# Booster_PA_OUT.net
KiCad netlist of a schematic drawn in Altium Designer
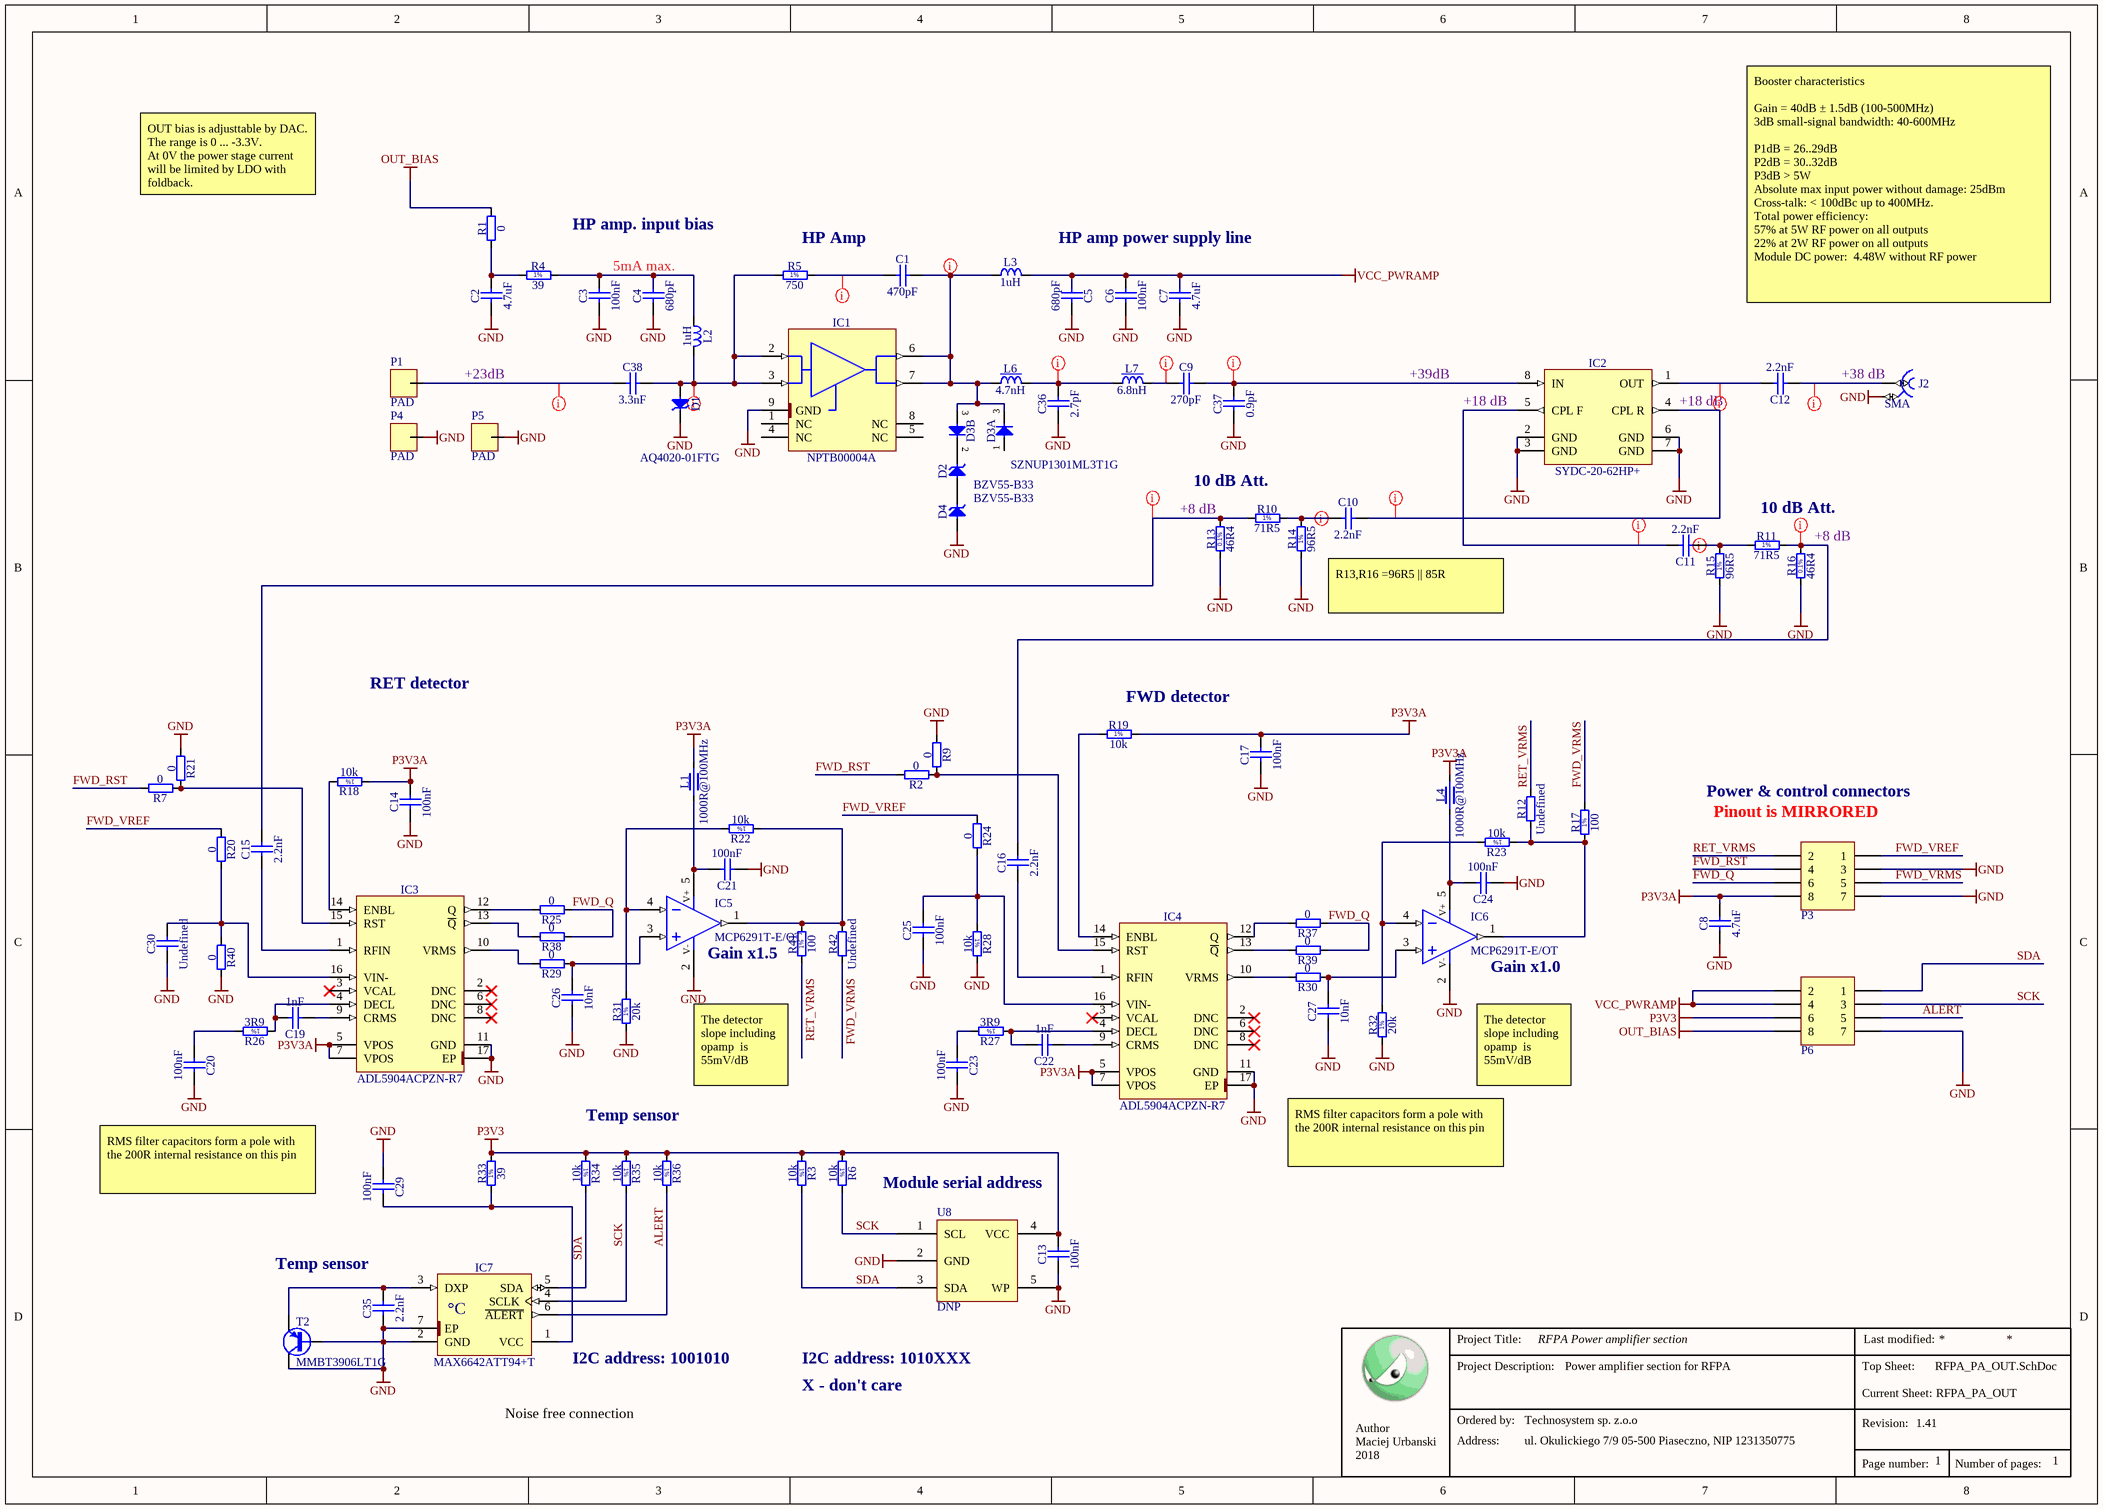
[diagram p0: Booster_PA_OUT.SchDoc]

(export (version "E")
  (design (tool "Eeschema 10.0.6"))
  (components
    (comp (ref "C1")
      (value "470pF")
      (footprint "CAPC1608X87N")
      (description "Non-polarised capacitor")
      (fields (field (name "PART NUMBER") "CC0603_470PF_50V_1%_NP0") (field (name "VOLTAGE") "50V"))
      (libsource (lib "Passives_RC") (part "CC0603_470PF_50V_1%_NP0"))
    )
    (comp (ref "C2")
      (value "4.7uF")
      (footprint "CAPC1709X95N")
      (description "Non-polarised capacitor")
      (fields
        (field (name "MANUFACTURER") "GENERIC")
        (field (name "MANUFACTURER PART NUMBER") "CC0603_4.7UF_16V_10%_X5R")
      )
      (libsource (lib "Capacitors") (part "Capacitor - non polarized"))
    )
    (comp (ref "C3")
      (value "100nF")
      (footprint "CAPC1005X55N")
      (description "Non-polarised capacitor")
      (fields
        (field (name "MANUFACTURER") "GENERIC")
        (field (name "MANUFACTURER PART NUMBER") "CC0402_100NF_50V_10%_X7R")
      )
      (libsource (lib "Capacitors") (part "Capacitor - non polarized"))
    )
    (comp (ref "C4")
      (value "680pF")
      (footprint "CAPC1608X87N")
      (description "Non-polarised capacitor")
      (fields
        (field (name "MANUFACTURER") "GENERIC")
        (field (name "MANUFACTURER PART NUMBER") "CC0603_680PF_50V_5%_NP0")
      )
      (libsource (lib "Capacitors") (part "Capacitor - non polarized"))
    )
    (comp (ref "C5")
      (value "680pF")
      (footprint "CAPC1608X87N")
      (description "Non-polarised capacitor")
      (fields
        (field (name "MANUFACTURER") "GENERIC")
        (field (name "MANUFACTURER PART NUMBER") "CC0603_680PF_50V_5%_NP0")
      )
      (libsource (lib "Capacitors") (part "Capacitor - non polarized"))
    )
    (comp (ref "C6")
      (value "100nF")
      (footprint "CAPC1005X55N")
      (description "Non-polarised capacitor")
      (fields
        (field (name "MANUFACTURER") "GENERIC")
        (field (name "MANUFACTURER PART NUMBER") "CC0402_100NF_50V_10%_X7R")
      )
      (libsource (lib "Capacitors") (part "Capacitor - non polarized"))
    )
    (comp (ref "C7")
      (value "4.7uF")
      (footprint "CAPC3225X270N")
      (description "Non-polarised capacitor")
      (fields (field (name "PART NUMBER") "CC1210_4.7UF_50V_10%_X7R") (field (name "VOLTAGE") "50V"))
      (libsource (lib "Capacitors") (part "Capacitor - non polarized"))
    )
    (comp (ref "C8")
      (value "4.7uF")
      (footprint "CAPC1709X95N")
      (description "Non-polarised capacitor")
      (fields
        (field (name "MANUFACTURER") "GENERIC")
        (field (name "MANUFACTURER PART NUMBER") "CC0603_4.7UF_16V_10%_X5R")
      )
      (libsource (lib "Capacitors") (part "Capacitor - non polarized"))
    )
    (comp (ref "C9")
      (value "270pF")
      (footprint "CAPC1608X87N")
      (description "Non-polarised capacitor")
      (fields (field (name "PART NUMBER") "CC0603_270PF_50V_1%_NP0") (field (name "VOLTAGE") "50V"))
      (libsource (lib "Passives_RC") (part "CC0603_270PF_50V_1%_NP0"))
    )
    (comp (ref "C10")
      (value "2.2nF")
      (footprint "CAPC1608X87N")
      (description "Non-polarised capacitor")
      (fields (field (name "PART NUMBER") "CC0603_2.2NF_50V_5%_C0G") (field (name "VOLTAGE") "50V"))
      (libsource (lib "Capacitors") (part "Capacitor - non polarized"))
    )
    (comp (ref "C11")
      (value "2.2nF")
      (footprint "CAPC1608X87N")
      (description "Non-polarised capacitor")
      (fields
        (field (name "MANUFACTURER") "GENERIC")
        (field (name "MANUFACTURER PART NUMBER") "CC0603_2.2NF_50V_5%_C0G")
      )
      (libsource (lib "Capacitors") (part "Capacitor - non polarized"))
    )
    (comp (ref "C12")
      (value "2.2nF")
      (footprint "CAPC1608X87N")
      (description "Non-polarised capacitor")
      (fields
        (field (name "MANUFACTURER") "GENERIC")
        (field (name "MANUFACTURER PART NUMBER") "CC0603_2.2NF_50V_5%_C0G")
      )
      (libsource (lib "Capacitors") (part "Capacitor - non polarized"))
    )
    (comp (ref "C13")
      (value "100nF")
      (footprint "CAPC1005X55N")
      (description "Non-polarised capacitor")
      (fields
        (field (name "MANUFACTURER") "GENERIC")
        (field (name "MANUFACTURER PART NUMBER") "CC0402_100NF_50V_10%_X7R")
      )
      (libsource (lib "Capacitors") (part "Capacitor - non polarized"))
    )
    (comp (ref "C14")
      (value "100nF")
      (footprint "CAPC1005X55N")
      (description "Non-polarised capacitor")
      (fields
        (field (name "MANUFACTURER") "GENERIC")
        (field (name "MANUFACTURER PART NUMBER") "CC0402_100NF_50V_10%_X7R")
      )
      (libsource (lib "Capacitors") (part "Capacitor - non polarized"))
    )
    (comp (ref "C15")
      (value "2.2nF")
      (footprint "CAPC1608X87N")
      (description "Non-polarised capacitor")
      (fields
        (field (name "MANUFACTURER") "GENERIC")
        (field (name "MANUFACTURER PART NUMBER") "CC0603_2.2NF_50V_5%_C0G")
      )
      (libsource (lib "Capacitors") (part "Capacitor - non polarized"))
    )
    (comp (ref "C16")
      (value "2.2nF")
      (footprint "CAPC1608X87N")
      (description "Non-polarised capacitor")
      (fields
        (field (name "MANUFACTURER") "GENERIC")
        (field (name "MANUFACTURER PART NUMBER") "CC0603_2.2NF_50V_5%_C0G")
      )
      (libsource (lib "Capacitors") (part "Capacitor - non polarized"))
    )
    (comp (ref "C17")
      (value "100nF")
      (footprint "CAPC1005X55N")
      (description "Non-polarised capacitor")
      (fields
        (field (name "MANUFACTURER") "GENERIC")
        (field (name "MANUFACTURER PART NUMBER") "CC0402_100NF_50V_10%_X7R")
      )
      (libsource (lib "Capacitors") (part "Capacitor - non polarized"))
    )
    (comp (ref "C19")
      (value "1nF")
      (footprint "CAPC1005X55N")
      (description "Non-polarised capacitor")
      (fields (field (name "PART NUMBER") "CC0402_1NF_50V_10%_X7R") (field (name "VOLTAGE") "50V"))
      (libsource (lib "Capacitors") (part "Capacitor - non polarized"))
    )
    (comp (ref "C20")
      (value "100nF")
      (footprint "CAPC1005X55N")
      (description "Non-polarised capacitor")
      (fields
        (field (name "MANUFACTURER") "GENERIC")
        (field (name "MANUFACTURER PART NUMBER") "CC0402_100NF_50V_10%_X7R")
      )
      (libsource (lib "Capacitors") (part "Capacitor - non polarized"))
    )
    (comp (ref "C21")
      (value "100nF")
      (footprint "CAPC1005X55N")
      (description "Non-polarised capacitor")
      (fields
        (field (name "MANUFACTURER") "GENERIC")
        (field (name "MANUFACTURER PART NUMBER") "CC0402_100NF_50V_10%_X7R")
      )
      (libsource (lib "Capacitors") (part "Capacitor - non polarized"))
    )
    (comp (ref "C22")
      (value "1nF")
      (footprint "CAPC1005X55N")
      (description "Non-polarised capacitor")
      (fields (field (name "PART NUMBER") "CC0402_1NF_50V_10%_X7R") (field (name "VOLTAGE") "50V"))
      (libsource (lib "Capacitors") (part "Capacitor - non polarized"))
    )
    (comp (ref "C23")
      (value "100nF")
      (footprint "CAPC1005X55N")
      (description "Non-polarised capacitor")
      (fields
        (field (name "MANUFACTURER") "GENERIC")
        (field (name "MANUFACTURER PART NUMBER") "CC0402_100NF_50V_10%_X7R")
      )
      (libsource (lib "Capacitors") (part "Capacitor - non polarized"))
    )
    (comp (ref "C24")
      (value "100nF")
      (footprint "CAPC1005X55N")
      (description "Non-polarised capacitor")
      (fields
        (field (name "MANUFACTURER") "GENERIC")
        (field (name "MANUFACTURER PART NUMBER") "CC0402_100NF_50V_10%_X7R")
      )
      (libsource (lib "Capacitors") (part "Capacitor - non polarized"))
    )
    (comp (ref "C25")
      (value "100nF")
      (footprint "CAPC1005X55N")
      (description "Non-polarised capacitor")
      (fields
        (field (name "MANUFACTURER") "GENERIC")
        (field (name "MANUFACTURER PART NUMBER") "CC0402_100NF_50V_10%_X7R")
      )
      (libsource (lib "Capacitors") (part "Capacitor - non polarized"))
    )
    (comp (ref "C26")
      (value "10nF")
      (footprint "CAPC1005X55N")
      (description "Non-polarised capacitor")
      (fields
        (field (name "MANUFACTURER") "GENERIC")
        (field (name "MANUFACTURER PART NUMBER") "CC0402_10NF_25V_10%_X7R")
      )
      (libsource (lib "Capacitors") (part "Capacitor - non polarized"))
    )
    (comp (ref "C27")
      (value "10nF")
      (footprint "CAPC1005X55N")
      (description "Non-polarised capacitor")
      (fields
        (field (name "MANUFACTURER") "GENERIC")
        (field (name "MANUFACTURER PART NUMBER") "CC0402_10NF_25V_10%_X7R")
      )
      (libsource (lib "Capacitors") (part "Capacitor - non polarized"))
    )
    (comp (ref "C29")
      (value "100nF")
      (footprint "CAPC1005X55N")
      (description "Non-polarised capacitor")
      (fields
        (field (name "MANUFACTURER") "GENERIC")
        (field (name "MANUFACTURER PART NUMBER") "CC0402_100NF_50V_10%_X7R")
      )
      (libsource (lib "Capacitors") (part "Capacitor - non polarized"))
    )
    (comp (ref "C30")
      (value "Undefined")
      (footprint "CAPC1608X90N")
      (description "Non-polarised capacitor")
      (fields (field (name "PART NUMBER") "CC0603_NO-VALUE"))
      (libsource (lib "Capacitors") (part "Capacitor - non polarized"))
    )
    (comp (ref "C35")
      (value "2.2nF")
      (footprint "CAPC1608X87N")
      (description "Non-polarised capacitor")
      (fields
        (field (name "MANUFACTURER") "GENERIC")
        (field (name "MANUFACTURER PART NUMBER") "CC0603_2.2NF_50V_5%_C0G")
      )
      (libsource (lib "Capacitors") (part "Capacitor - non polarized"))
    )
    (comp (ref "C36")
      (value "2.7pF")
      (footprint "CAPC1608X87N")
      (description "Non-polarised capacitor")
      (fields (field (name "PART NUMBER") "CC0603_2.7PF_50V_0.25PF_NP0") (field (name "VOLTAGE") "50V"))
      (libsource (lib "Capacitors") (part "Capacitor - non polarized"))
    )
    (comp (ref "C37")
      (value "0.9pF")
      (footprint "CAPC1608X87N")
      (description "Non-polarised capacitor")
      (fields (field (name "PART NUMBER") "CC0603_0.9PF_50V_0.05PF_NP0") (field (name "VOLTAGE") "50V"))
      (libsource (lib "Passives_RC") (part "CC0603_0.9PF_50V_0.05PF_NP0"))
    )
    (comp (ref "C38")
      (value "3.3nF")
      (footprint "CAPC1608X87N")
      (description "Non-polarised capacitor")
      (fields
        (field (name "MANUFACTURER") "GENERIC")
        (field (name "MANUFACTURER PART NUMBER") "CC0603_3.3NF_50V_5%_C0G")
      )
      (libsource (lib "Capacitors") (part "Capacitor - non polarized"))
    )
    (comp (ref "D1")
      (value "AQ4020-01FTG")
      (footprint "SOD2512X110N")
      (description "4V Transient Voltage Suppressor Diode (Uni-Directional)")
      (fields (field (name "VOLTAGE") "4V") (field (name "POWER") "735W"))
      (libsource (lib "Diodes") (part "D_TVS_AQ4020-01FTG"))
    )
    (comp (ref "D2")
      (value "BZV55-B33")
      (footprint "DIOMELF3515N")
      (description "Zener Diode")
      (fields (field (name "VOLTAGE") "33V") (field (name "POWER") "500mW"))
      (libsource (lib "ICs And Semiconductors") (part "Diode Zener"))
    )
    (comp (ref "D3")
      (value "SZNUP1301ML3T1G")
      (footprint "SOT95P240X110-3N")
      (description "Low Capacitance Diode Array for ESD Protection in a Single Data Line")
      (fields (field (name "VOLTAGE") "70V") (field (name "POWER") "215mA"))
      (libsource (lib "Diodes") (part "D_TVS_SZNUP1301ML3T1G"))
    )
    (comp (ref "D4")
      (value "BZV55-B33")
      (footprint "DIOMELF3515N")
      (description "Zener Diode")
      (fields (field (name "VOLTAGE") "33V") (field (name "POWER") "500mW"))
      (libsource (lib "ICs And Semiconductors") (part "Diode Zener"))
    )
    (comp (ref "IC1")
      (value "NPTB00004A")
      (footprint "SOIC127P610X167-9N-R245X335")
      (description "GaN Wideband Transistor 28V, 5W, DC - 6GHz")
      (fields (field (name "MANUFACTURER") "MACOM"))
      (libsource (lib "ICs And Semiconductors") (part "NPTB00004A"))
    )
    (comp (ref "IC2")
      (value "SYDC-20-62HP+")
      (footprint "MINI-CIRCUITS_AH202-1")
      (description "50Ohm, 10 to 540MHz, 25W, 20dB Bi-Directional Coupler")
      (fields (field (name "MANUFACTURER") "MINI-CIRCUITS"))
      (libsource (lib "ICs And Semiconductors") (part "SYDC-20-62HP+"))
    )
    (comp (ref "IC3")
      (value "ADL5904ACPZN-R7")
      (footprint "QFN50P300X300X80-17N-S175")
      (description "DC to 6 GHz, 45 dB TruPwr Detector With Envelope Threshold Detection")
      (fields (field (name "MANUFACTURER") "ANALOG DEVICES"))
      (libsource (lib "ICs And Semiconductors") (part "ADL5904"))
    )
    (comp (ref "IC4")
      (value "ADL5904ACPZN-R7")
      (footprint "QFN50P300X300X80-17N-S175")
      (description "DC to 6 GHz, 45 dB TruPwr Detector With Envelope Threshold Detection")
      (fields (field (name "MANUFACTURER") "ANALOG DEVICES"))
      (libsource (lib "ICs And Semiconductors") (part "ADL5904"))
    )
    (comp (ref "IC5")
      (value "MCP6291T-E/OT")
      (footprint "SOT95P270X145-5N")
      (description "Operational Amplifier")
      (fields (field (name "MANUFACTURER") "MICROCHIP TECHNOLOGY"))
      (libsource (lib "ICs And Semiconductors") (part "Operational Amplifier Type7"))
    )
    (comp (ref "IC6")
      (value "MCP6291T-E/OT")
      (footprint "SOT95P270X145-5N")
      (description "Operational Amplifier")
      (fields (field (name "MANUFACTURER") "MICROCHIP TECHNOLOGY"))
      (libsource (lib "ICs And Semiconductors") (part "Operational Amplifier Type7"))
    )
    (comp (ref "IC7")
      (value "MAX6642ATT94+T")
      (footprint "SON95P300X300X80-7N-R160X240")
      (description "±1°C, SMBus-Compatible Remote/Local Temperature Sensor with Overtemperature Alarm")
      (fields (field (name "MANUFACTURER") "MAXIM"))
      (libsource (lib "ICs And Semiconductors") (part "MAX6642ATT"))
    )
    (comp (ref "J2")
      (value "SMA")
      (footprint "MOLEX_73251-2120")
      (description "50 Ohm, SMA Edge Mount PCB, With Jam Nut And Lock Washer")
      (fields (field (name "PART NUMBER") "MOLEX_73251-2120") (field (name "MANUFACTURER") "MOLEX"))
      (libsource (lib "Connectors") (part "CON_SMA_RA_SMD_73251-2120"))
    )
    (comp (ref "L1")
      (value "1000R@100MHz")
      (footprint "INDC1608X95N")
      (fields
        (field (name "MANUFACTURER") "MURATA")
        (field (name "MANUFACTURER PART NUMBER") "BLM18HE102SN1")
        (field (name "PART NUMBER") "IND0603_MURATA_BLM18HE102SN1")
      )
      (libsource (lib "Inductors & Transformers") (part "Ferrite Bead"))
    )
    (comp (ref "L2")
      (value "1uH")
      (footprint "INDC2113X60N")
      (description "Inductor")
      (fields (field (name "PART NUMBER") "IND0805_1UH_20%_WURTH_74479773210") (field (name "POWER") "800mA"))
      (libsource (lib "") (part "Inductor_1"))
    )
    (comp (ref "L3")
      (value "1uH")
      (footprint "INDC2113X60N")
      (description "Inductor")
      (fields (field (name "PART NUMBER") "IND0805_1UH_20%_WURTH_74479773210") (field (name "POWER") "800mA"))
      (libsource (lib "Inductors & Transformers") (part "Inductor"))
    )
    (comp (ref "L4")
      (value "1000R@100MHz")
      (footprint "INDC1608X95N")
      (fields
        (field (name "MANUFACTURER") "MURATA")
        (field (name "MANUFACTURER PART NUMBER") "BLM18HE102SN1")
        (field (name "PART NUMBER") "IND0603_MURATA_BLM18HE102SN1")
      )
      (libsource (lib "Inductors & Transformers") (part "Ferrite Bead"))
    )
    (comp (ref "L6")
      (value "4.7nH")
      (footprint "IND_MURATA_LQW18AN_G8")
      (description "Inductor With Core")
      (fields
        (field (name "PART NUMBER") "IND0603_4.7NH_2%_MURATA_LQW18AN4N7G8Z")
        (field (name "POWER") "1.5A")
      )
      (libsource (lib "Inductors & Transformers") (part "Inductor With Magnetic core"))
    )
    (comp (ref "L7")
      (value "6.8nH")
      (footprint "IND_MURATA_LQW18AN_G8")
      (description "Inductor With Core")
      (fields
        (field (name "PART NUMBER") "IND0603_6.8NH_2%_MURATA_LQW18AN6N8G8Z")
        (field (name "POWER") "1.9A")
      )
      (libsource (lib "Inductors & Transformers") (part "Inductor With Magnetic core"))
    )
    (comp (ref "P1")
      (value "PAD")
      (footprint "PAD_2x3_rect")
      (libsource (lib "elementy_stykowe") (part "PAD"))
    )
    (comp (ref "P3")
      (value "HDR2X4")
      (footprint "HDR2X4_SMD")
      (description "Header, 4-Pin, Dual Row")
      (libsource (lib "onyks") (part "HDR2X4"))
    )
    (comp (ref "P4")
      (value "PAD")
      (footprint "PAD_2x3_rect")
      (libsource (lib "elementy_stykowe") (part "PAD"))
    )
    (comp (ref "P5")
      (value "PAD")
      (footprint "PAD_2x3_rect")
      (libsource (lib "elementy_stykowe") (part "PAD"))
    )
    (comp (ref "P6")
      (value "HDR2X4")
      (footprint "HDR2X4_SMD")
      (description "Header, 4-Pin, Dual Row")
      (libsource (lib "onyks") (part "HDR2X4"))
    )
    (comp (ref "R1")
      (value "0")
      (footprint "RESC1005X40N")
      (description "Resistor")
      (fields
        (field (name "MANUFACTURER") "GENERIC")
        (field (name "MANUFACTURER PART NUMBER") "R0402_0R_JUMPER")
      )
      (libsource (lib "Resistors") (part "Resistor"))
    )
    (comp (ref "R2")
      (value "0")
      (footprint "RESC1005X40N")
      (description "Resistor")
      (fields
        (field (name "MANUFACTURER") "GENERIC")
        (field (name "MANUFACTURER PART NUMBER") "R0402_0R_JUMPER")
      )
      (libsource (lib "Resistors") (part "Resistor"))
    )
    (comp (ref "R3")
      (value "10k")
      (footprint "RESC1005X40N")
      (description "Resistor - 1%")
      (fields
        (field (name "MANUFACTURER") "GENERIC")
        (field (name "MANUFACTURER PART NUMBER") "R0402_10K_1%_0.0625W_100PPM")
      )
      (libsource (lib "Resistors") (part "Resistor - 1%"))
    )
    (comp (ref "R4")
      (value "39")
      (footprint "RESC1608X55N")
      (description "Resistor - 1%")
      (fields (field (name "PART NUMBER") "R0603_39R_1%_0.1W_100PPM") (field (name "POWER") "0.1W"))
      (libsource (lib "Resistors") (part "Resistor - 1%"))
    )
    (comp (ref "R5")
      (value "750")
      (footprint "RESC1608X55N")
      (description "Resistor - 1%")
      (fields (field (name "PART NUMBER") "R0603_750R_1%_0.1W_100PPM") (field (name "POWER") "0.1W"))
      (libsource (lib "Resistors") (part "Resistor - 1%"))
    )
    (comp (ref "R6")
      (value "10k")
      (footprint "RESC1005X40N")
      (description "Resistor - 1%")
      (fields
        (field (name "MANUFACTURER") "GENERIC")
        (field (name "MANUFACTURER PART NUMBER") "R0402_10K_1%_0.0625W_100PPM")
      )
      (libsource (lib "Resistors") (part "Resistor - 1%"))
    )
    (comp (ref "R7")
      (value "0")
      (footprint "RESC1005X40N")
      (description "Resistor")
      (fields
        (field (name "MANUFACTURER") "GENERIC")
        (field (name "MANUFACTURER PART NUMBER") "R0402_0R_JUMPER")
      )
      (libsource (lib "Resistors") (part "Resistor"))
    )
    (comp (ref "R9")
      (value "0")
      (footprint "RESC1005X40N")
      (description "Resistor")
      (fields
        (field (name "MANUFACTURER") "GENERIC")
        (field (name "MANUFACTURER PART NUMBER") "R0402_0R_JUMPER")
      )
      (libsource (lib "Resistors") (part "Resistor"))
    )
    (comp (ref "R10")
      (value "71R5")
      (footprint "RESC1608X55N")
      (description "Resistor - 1%")
      (fields (field (name "PART NUMBER") "R0603_71R5_1%_0.1W_100PPM") (field (name "POWER") "0.1W"))
      (libsource (lib "Resistors") (part "Resistor - 1%"))
    )
    (comp (ref "R11")
      (value "71R5")
      (footprint "RESC1608X55N")
      (description "Resistor - 1%")
      (fields (field (name "PART NUMBER") "R0603_71R5_1%_0.1W_100PPM") (field (name "POWER") "0.1W"))
      (libsource (lib "Resistors") (part "Resistor - 1%"))
    )
    (comp (ref "R12")
      (value "Undefined")
      (footprint "RESC1608X55N")
      (description "Resistor")
      (fields (field (name "MANUFACTURER PART NUMBER") "R0603_NO-VALUE"))
      (libsource (lib "Resistors") (part "Resistor"))
    )
    (comp (ref "R13")
      (value "46R4")
      (footprint "RESC1608X55N")
      (description "Resistor - 0.1%")
      (fields (field (name "PART NUMBER") "R0603_46R4_0.1%_0.063W_10PPM") (field (name "POWER") "0.063W"))
      (libsource (lib "Resistors") (part "Resistor - 0.1%"))
    )
    (comp (ref "R14")
      (value "96R5")
      (footprint "RESC1608X55N")
      (description "Resistor - 0.5%")
      (fields (field (name "PART NUMBER") "R0603_96R5_0.5%_0.1W_50PPM") (field (name "POWER") "0.1W"))
      (libsource (lib "Passives_RC") (part "R0603_96R5_0.5%_0.1W_50PPM"))
    )
    (comp (ref "R15")
      (value "96R5")
      (footprint "RESC1608X55N")
      (description "Resistor - 0.5%")
      (fields (field (name "PART NUMBER") "R0603_96R5_0.5%_0.1W_50PPM") (field (name "POWER") "0.1W"))
      (libsource (lib "Passives_RC") (part "R0603_96R5_0.5%_0.1W_50PPM"))
    )
    (comp (ref "R16")
      (value "46R4")
      (footprint "RESC1608X55N")
      (description "Resistor - 0.1%")
      (fields (field (name "PART NUMBER") "R0603_46R4_0.1%_0.063W_10PPM") (field (name "POWER") "0.063W"))
      (libsource (lib "Resistors") (part "Resistor - 0.1%"))
    )
    (comp (ref "R17")
      (value "100")
      (footprint "RESC1608X55N")
      (description "Resistor - 1%")
      (fields
        (field (name "MANUFACTURER") "GENERIC")
        (field (name "MANUFACTURER PART NUMBER") "R0603_100R_1%_0.1W_100PPM")
      )
      (libsource (lib "Resistors") (part "Resistor - 1%"))
    )
    (comp (ref "R18")
      (value "10k")
      (footprint "RESC1005X40N")
      (description "Resistor - 1%")
      (fields
        (field (name "MANUFACTURER") "GENERIC")
        (field (name "MANUFACTURER PART NUMBER") "R0402_10K_1%_0.0625W_100PPM")
      )
      (libsource (lib "Resistors") (part "Resistor - 1%"))
    )
    (comp (ref "R19")
      (value "10k")
      (footprint "RESC1005X40N")
      (description "Resistor - 1%")
      (fields (field (name "PART NUMBER") "R0402_10K_1%_0.0625W_100PPM") (field (name "POWER") "0.0625W"))
      (libsource (lib "Resistors") (part "Resistor - 1%"))
    )
    (comp (ref "R20")
      (value "0")
      (footprint "RESC1005X40N")
      (description "Resistor")
      (fields
        (field (name "MANUFACTURER") "GENERIC")
        (field (name "MANUFACTURER PART NUMBER") "R0402_0R_JUMPER")
      )
      (libsource (lib "Resistors") (part "Resistor"))
    )
    (comp (ref "R21")
      (value "0")
      (footprint "RESC1005X40N")
      (description "Resistor")
      (fields
        (field (name "MANUFACTURER") "GENERIC")
        (field (name "MANUFACTURER PART NUMBER") "R0402_0R_JUMPER")
      )
      (libsource (lib "Resistors") (part "Resistor"))
    )
    (comp (ref "R22")
      (value "10k")
      (footprint "RESC1005X40N")
      (description "Resistor - 1%")
      (fields
        (field (name "MANUFACTURER") "GENERIC")
        (field (name "MANUFACTURER PART NUMBER") "R0402_10K_1%_0.0625W_100PPM")
      )
      (libsource (lib "Resistors") (part "Resistor - 1%"))
    )
    (comp (ref "R23")
      (value "10k")
      (footprint "RESC1005X40N")
      (description "Resistor - 1%")
      (fields
        (field (name "MANUFACTURER") "GENERIC")
        (field (name "MANUFACTURER PART NUMBER") "R0402_10K_1%_0.0625W_100PPM")
      )
      (libsource (lib "Resistors") (part "Resistor - 1%"))
    )
    (comp (ref "R24")
      (value "0")
      (footprint "RESC1005X40N")
      (description "Resistor")
      (fields
        (field (name "MANUFACTURER") "GENERIC")
        (field (name "MANUFACTURER PART NUMBER") "R0402_0R_JUMPER")
      )
      (libsource (lib "Resistors") (part "Resistor"))
    )
    (comp (ref "R25")
      (value "0")
      (footprint "RESC1005X40N")
      (description "Resistor")
      (fields
        (field (name "MANUFACTURER") "GENERIC")
        (field (name "MANUFACTURER PART NUMBER") "R0402_0R_JUMPER")
      )
      (libsource (lib "Resistors") (part "Resistor"))
    )
    (comp (ref "R26")
      (value "3R9")
      (footprint "RESC1005X40N")
      (description "Resistor - 1%")
      (fields (field (name "PART NUMBER") "R0402_3R9_1%_0.0625W_200PPM") (field (name "POWER") "0.0625W"))
      (libsource (lib "Resistors") (part "Resistor - 1%"))
    )
    (comp (ref "R27")
      (value "3R9")
      (footprint "RESC1005X40N")
      (description "Resistor - 1%")
      (fields (field (name "PART NUMBER") "R0402_3R9_1%_0.0625W_200PPM") (field (name "POWER") "0.0625W"))
      (libsource (lib "Resistors") (part "Resistor - 1%"))
    )
    (comp (ref "R28")
      (value "10k")
      (footprint "RESC1005X40N")
      (description "Resistor - 1%")
      (fields
        (field (name "MANUFACTURER") "GENERIC")
        (field (name "MANUFACTURER PART NUMBER") "R0402_10K_1%_0.0625W_100PPM")
      )
      (libsource (lib "Resistors") (part "Resistor - 1%"))
    )
    (comp (ref "R29")
      (value "0")
      (footprint "RESC1005X40N")
      (description "Resistor")
      (fields
        (field (name "MANUFACTURER") "GENERIC")
        (field (name "MANUFACTURER PART NUMBER") "R0402_0R_JUMPER")
      )
      (libsource (lib "Resistors") (part "Resistor"))
    )
    (comp (ref "R30")
      (value "0")
      (footprint "RESC1005X40N")
      (description "Resistor")
      (fields
        (field (name "MANUFACTURER") "GENERIC")
        (field (name "MANUFACTURER PART NUMBER") "R0402_0R_JUMPER")
      )
      (libsource (lib "Resistors") (part "Resistor"))
    )
    (comp (ref "R31")
      (value "20k")
      (footprint "RESC1608X55N")
      (description "Resistor - 1%")
      (fields (field (name "PART NUMBER") "R0603_20K_1%_0.1W_100PPM") (field (name "POWER") "0.1W"))
      (libsource (lib "Resistors") (part "Resistor - 1%"))
    )
    (comp (ref "R32")
      (value "20k")
      (footprint "RESC1608X55N")
      (description "Resistor - 1%")
      (fields (field (name "PART NUMBER") "R0603_20K_1%_0.1W_100PPM") (field (name "POWER") "0.1W"))
      (libsource (lib "Resistors") (part "Resistor - 1%"))
    )
    (comp (ref "R33")
      (value "39")
      (footprint "RESC1608X55N")
      (description "Resistor - 1%")
      (fields (field (name "PART NUMBER") "R0603_39R_1%_0.1W_100PPM") (field (name "POWER") "0.1W"))
      (libsource (lib "Resistors") (part "Resistor - 1%"))
    )
    (comp (ref "R34")
      (value "10k")
      (footprint "RESC1005X40N")
      (description "Resistor - 1%")
      (fields
        (field (name "MANUFACTURER") "GENERIC")
        (field (name "MANUFACTURER PART NUMBER") "R0402_10K_1%_0.0625W_100PPM")
      )
      (libsource (lib "Resistors") (part "Resistor - 1%"))
    )
    (comp (ref "R35")
      (value "10k")
      (footprint "RESC1005X40N")
      (description "Resistor - 1%")
      (fields
        (field (name "MANUFACTURER") "GENERIC")
        (field (name "MANUFACTURER PART NUMBER") "R0402_10K_1%_0.0625W_100PPM")
      )
      (libsource (lib "Resistors") (part "Resistor - 1%"))
    )
    (comp (ref "R36")
      (value "10k")
      (footprint "RESC1005X40N")
      (description "Resistor - 1%")
      (fields
        (field (name "MANUFACTURER") "GENERIC")
        (field (name "MANUFACTURER PART NUMBER") "R0402_10K_1%_0.0625W_100PPM")
      )
      (libsource (lib "Resistors") (part "Resistor - 1%"))
    )
    (comp (ref "R37")
      (value "0")
      (footprint "RESC1005X40N")
      (description "Resistor")
      (fields
        (field (name "MANUFACTURER") "GENERIC")
        (field (name "MANUFACTURER PART NUMBER") "R0402_0R_JUMPER")
      )
      (libsource (lib "Resistors") (part "Resistor"))
    )
    (comp (ref "R38")
      (value "0")
      (footprint "RESC1005X40N")
      (description "Resistor")
      (fields
        (field (name "MANUFACTURER") "GENERIC")
        (field (name "MANUFACTURER PART NUMBER") "R0402_0R_JUMPER")
      )
      (libsource (lib "Resistors") (part "Resistor"))
    )
    (comp (ref "R39")
      (value "0")
      (footprint "RESC1005X40N")
      (description "Resistor")
      (fields
        (field (name "MANUFACTURER") "GENERIC")
        (field (name "MANUFACTURER PART NUMBER") "R0402_0R_JUMPER")
      )
      (libsource (lib "Resistors") (part "Resistor"))
    )
    (comp (ref "R40")
      (value "0")
      (footprint "RESC1005X40N")
      (description "Resistor")
      (fields
        (field (name "MANUFACTURER") "GENERIC")
        (field (name "MANUFACTURER PART NUMBER") "R0402_0R_JUMPER")
      )
      (libsource (lib "Resistors") (part "Resistor"))
    )
    (comp (ref "R41")
      (value "100")
      (footprint "RESC1608X55N")
      (description "Resistor - 1%")
      (fields
        (field (name "MANUFACTURER") "GENERIC")
        (field (name "MANUFACTURER PART NUMBER") "R0603_100R_1%_0.1W_100PPM")
      )
      (libsource (lib "Resistors") (part "Resistor - 1%"))
    )
    (comp (ref "R42")
      (value "Undefined")
      (footprint "RESC1608X55N")
      (description "Resistor")
      (fields (field (name "MANUFACTURER PART NUMBER") "R0603_NO-VALUE"))
      (libsource (lib "Resistors") (part "Resistor"))
    )
    (comp (ref "T2")
      (value "MMBT3906LT1G")
      (footprint "SOT95P240X110-3N")
      (description "PNP Transistor")
      (fields (field (name "MANUFACTURER") "ON SEMICONDUCTOR"))
      (libsource (lib "ICs And Semiconductors") (part "PNP B1 E2 C3"))
    )
    (comp (ref "U8")
      (value "DNP")
      (footprint "SOT23-5_N")
      (description "1K I2  C™ Serial EEPROM with Half-Array Write-Protect")
      (fields (field (name "MANUFACTURER") "Microchip"))
      (libsource (lib "uklady_cyfrowe") (part "24AA01H"))
    )
  )
  (nets
    (net (code "1") (name "/ALERT") (class "Default")
      (node (ref "IC7") (pin "6") (pinfunction "~{ALERT}_6") (pintype "output"))
      (node (ref "P6") (pin "5") (pinfunction "5_5") (pintype "passive"))
      (node (ref "R36") (pin "2") (pinfunction "2_2") (pintype "passive"))
    )
    (net (code "2") (name "/FWD_Q") (class "Default")
      (node (ref "P3") (pin "6") (pinfunction "6_6") (pintype "passive"))
      (node (ref "R25") (pin "1") (pinfunction "1_1") (pintype "passive"))
      (node (ref "R37") (pin "1") (pinfunction "1_1") (pintype "passive"))
      (node (ref "R38") (pin "1") (pinfunction "1_1") (pintype "passive"))
      (node (ref "R39") (pin "1") (pinfunction "1_1") (pintype "passive"))
    )
    (net (code "3") (name "/FWD_RST") (class "Default")
      (node (ref "P3") (pin "4") (pinfunction "4_4") (pintype "passive"))
      (node (ref "R2") (pin "2") (pinfunction "2_2") (pintype "passive"))
      (node (ref "R7") (pin "2") (pinfunction "2_2") (pintype "passive"))
    )
    (net (code "4") (name "/FWD_VREF") (class "Default")
      (node (ref "P3") (pin "1") (pinfunction "1_1") (pintype "passive"))
      (node (ref "R20") (pin "1") (pinfunction "1_1") (pintype "passive"))
      (node (ref "R24") (pin "1") (pinfunction "1_1") (pintype "passive"))
    )
    (net (code "5") (name "/FWD_VRMS") (class "Default")
      (node (ref "P3") (pin "5") (pinfunction "5_5") (pintype "passive"))
      (node (ref "R17") (pin "2") (pinfunction "2_2") (pintype "passive"))
      (node (ref "R42") (pin "1") (pinfunction "1_1") (pintype "passive"))
    )
    (net (code "6") (name "/RET_VRMS") (class "Default")
      (node (ref "P3") (pin "2") (pinfunction "2_2") (pintype "passive"))
      (node (ref "R12") (pin "2") (pinfunction "2_2") (pintype "passive"))
      (node (ref "R41") (pin "1") (pinfunction "1_1") (pintype "passive"))
    )
    (net (code "7") (name "/SCK") (class "Default")
      (node (ref "IC7") (pin "4") (pinfunction "SCLK_4") (pintype "input"))
      (node (ref "P6") (pin "3") (pinfunction "3_3") (pintype "passive"))
      (node (ref "R35") (pin "2") (pinfunction "2_2") (pintype "passive"))
      (node (ref "R6") (pin "2") (pinfunction "2_2") (pintype "passive"))
      (node (ref "U8") (pin "1") (pinfunction "SCL_1") (pintype "passive"))
    )
    (net (code "8") (name "/SDA") (class "Default")
      (node (ref "IC7") (pin "5") (pinfunction "SDA_5") (pintype "bidirectional"))
      (node (ref "P6") (pin "1") (pinfunction "1_1") (pintype "passive"))
      (node (ref "R3") (pin "2") (pinfunction "2_2") (pintype "passive"))
      (node (ref "R34") (pin "2") (pinfunction "2_2") (pintype "passive"))
      (node (ref "U8") (pin "3") (pinfunction "SDA_3") (pintype "passive"))
    )
    (net (code "9") (name "GND") (class "Default")
      (node (ref "C13") (pin "1") (pinfunction "1_1") (pintype "passive"))
      (node (ref "C14") (pin "1") (pinfunction "1_1") (pintype "passive"))
      (node (ref "C17") (pin "1") (pinfunction "1_1") (pintype "passive"))
      (node (ref "C2") (pin "1") (pinfunction "1_1") (pintype "passive"))
      (node (ref "C20") (pin "2") (pinfunction "2_2") (pintype "passive"))
      (node (ref "C21") (pin "1") (pinfunction "1_1") (pintype "passive"))
      (node (ref "C23") (pin "2") (pinfunction "2_2") (pintype "passive"))
      (node (ref "C24") (pin "1") (pinfunction "1_1") (pintype "passive"))
      (node (ref "C25") (pin "1") (pinfunction "1_1") (pintype "passive"))
      (node (ref "C26") (pin "1") (pinfunction "1_1") (pintype "passive"))
      (node (ref "C27") (pin "1") (pinfunction "1_1") (pintype "passive"))
      (node (ref "C29") (pin "1") (pinfunction "1_1") (pintype "passive"))
      (node (ref "C3") (pin "1") (pinfunction "1_1") (pintype "passive"))
      (node (ref "C30") (pin "1") (pinfunction "1_1") (pintype "passive"))
      (node (ref "C35") (pin "1") (pinfunction "1_1") (pintype "passive"))
      (node (ref "C36") (pin "1") (pinfunction "1_1") (pintype "passive"))
      (node (ref "C37") (pin "1") (pinfunction "1_1") (pintype "passive"))
      (node (ref "C4") (pin "1") (pinfunction "1_1") (pintype "passive"))
      (node (ref "C5") (pin "1") (pinfunction "1_1") (pintype "passive"))
      (node (ref "C6") (pin "1") (pinfunction "1_1") (pintype "passive"))
      (node (ref "C7") (pin "1") (pinfunction "1_1") (pintype "passive"))
      (node (ref "C8") (pin "1") (pinfunction "1_1") (pintype "passive"))
      (node (ref "D1") (pin "1") (pinfunction "C_1") (pintype "passive"))
      (node (ref "D4") (pin "2") (pinfunction "A_2") (pintype "passive"))
      (node (ref "IC1") (pin "9") (pinfunction "GND_9") (pintype "power_in"))
      (node (ref "IC2") (pin "2") (pinfunction "GND_2") (pintype "power_in"))
      (node (ref "IC2") (pin "3") (pinfunction "GND_3") (pintype "power_in"))
      (node (ref "IC2") (pin "6") (pinfunction "GND_6") (pintype "power_in"))
      (node (ref "IC2") (pin "7") (pinfunction "GND_7") (pintype "power_in"))
      (node (ref "IC3") (pin "11") (pinfunction "GND_11") (pintype "power_in"))
      (node (ref "IC3") (pin "17") (pinfunction "EP_17") (pintype "power_in"))
      (node (ref "IC4") (pin "11") (pinfunction "GND_11") (pintype "power_in"))
      (node (ref "IC4") (pin "17") (pinfunction "EP_17") (pintype "power_in"))
      (node (ref "IC5") (pin "2") (pinfunction "V-_2") (pintype "power_in"))
      (node (ref "IC6") (pin "2") (pinfunction "V-_2") (pintype "power_in"))
      (node (ref "IC7") (pin "2") (pinfunction "GND_2") (pintype "power_in"))
      (node (ref "IC7") (pin "7") (pinfunction "EP_7") (pintype "power_in"))
      (node (ref "J2") (pin "2") (pinfunction "2_2") (pintype "bidirectional"))
      (node (ref "P3") (pin "3") (pinfunction "3_3") (pintype "passive"))
      (node (ref "P3") (pin "7") (pinfunction "7_7") (pintype "passive"))
      (node (ref "P4") (pin "1") (pinfunction "1_1") (pintype "passive"))
      (node (ref "P5") (pin "1") (pinfunction "1_1") (pintype "passive"))
      (node (ref "P6") (pin "7") (pinfunction "7_7") (pintype "passive"))
      (node (ref "R13") (pin "1") (pinfunction "1_1") (pintype "passive"))
      (node (ref "R14") (pin "1") (pinfunction "1_1") (pintype "passive"))
      (node (ref "R15") (pin "1") (pinfunction "1_1") (pintype "passive"))
      (node (ref "R16") (pin "1") (pinfunction "1_1") (pintype "passive"))
      (node (ref "R21") (pin "1") (pinfunction "1_1") (pintype "passive"))
      (node (ref "R28") (pin "2") (pinfunction "2_2") (pintype "passive"))
      (node (ref "R31") (pin "1") (pinfunction "1_1") (pintype "passive"))
      (node (ref "R32") (pin "1") (pinfunction "1_1") (pintype "passive"))
      (node (ref "R40") (pin "2") (pinfunction "2_2") (pintype "passive"))
      (node (ref "R9") (pin "1") (pinfunction "1_1") (pintype "passive"))
      (node (ref "T2") (pin "1") (pinfunction "B_1") (pintype "passive"))
      (node (ref "T2") (pin "3") (pinfunction "C_3") (pintype "passive"))
      (node (ref "U8") (pin "2") (pinfunction "GND_2") (pintype "passive"))
      (node (ref "U8") (pin "5") (pinfunction "WP_5") (pintype "passive"))
    )
    (net (code "10") (name "Net-(C1-Pad1)") (class "Default")
      (node (ref "C1") (pin "1") (pinfunction "1_1") (pintype "passive"))
      (node (ref "R5") (pin "2") (pinfunction "2_2") (pintype "passive"))
    )
    (net (code "11") (name "Net-(C2-Pad2)") (class "Default")
      (node (ref "C2") (pin "2") (pinfunction "2_2") (pintype "passive"))
      (node (ref "R1") (pin "1") (pinfunction "1_1") (pintype "passive"))
      (node (ref "R4") (pin "1") (pinfunction "1_1") (pintype "passive"))
    )
    (net (code "12") (name "Net-(C3-Pad2)") (class "Default")
      (node (ref "C3") (pin "2") (pinfunction "2_2") (pintype "passive"))
      (node (ref "C4") (pin "2") (pinfunction "2_2") (pintype "passive"))
      (node (ref "L2") (pin "1") (pinfunction "1_1") (pintype "passive"))
      (node (ref "R4") (pin "2") (pinfunction "2_2") (pintype "passive"))
    )
    (net (code "13") (name "Net-(C9-Pad1)") (class "Default")
      (node (ref "C9") (pin "1") (pinfunction "1_1") (pintype "passive"))
      (node (ref "L7") (pin "2") (pinfunction "2_2") (pintype "passive"))
    )
    (net (code "14") (name "Net-(C10-Pad1)") (class "Default")
      (node (ref "C10") (pin "1") (pinfunction "1_1") (pintype "passive"))
      (node (ref "R10") (pin "2") (pinfunction "2_2") (pintype "passive"))
      (node (ref "R14") (pin "2") (pinfunction "2_2") (pintype "passive"))
    )
    (net (code "15") (name "Net-(C11-Pad1)") (class "Default")
      (node (ref "C11") (pin "1") (pinfunction "1_1") (pintype "passive"))
      (node (ref "R11") (pin "1") (pinfunction "1_1") (pintype "passive"))
      (node (ref "R15") (pin "2") (pinfunction "2_2") (pintype "passive"))
    )
    (net (code "16") (name "Net-(C12-Pad1)") (class "Default")
      (node (ref "C12") (pin "1") (pinfunction "1_1") (pintype "passive"))
      (node (ref "J2") (pin "1") (pinfunction "1_1") (pintype "bidirectional"))
    )
    (net (code "17") (name "Net-(C15-Pad2)") (class "Default")
      (node (ref "C15") (pin "2") (pinfunction "2_2") (pintype "passive"))
      (node (ref "R10") (pin "1") (pinfunction "1_1") (pintype "passive"))
      (node (ref "R13") (pin "2") (pinfunction "2_2") (pintype "passive"))
    )
    (net (code "18") (name "Net-(C16-Pad2)") (class "Default")
      (node (ref "C16") (pin "2") (pinfunction "2_2") (pintype "passive"))
      (node (ref "R11") (pin "2") (pinfunction "2_2") (pintype "passive"))
      (node (ref "R16") (pin "2") (pinfunction "2_2") (pintype "passive"))
    )
    (net (code "19") (name "Net-(C20-Pad1)") (class "Default")
      (node (ref "C20") (pin "1") (pinfunction "1_1") (pintype "passive"))
      (node (ref "R26") (pin "2") (pinfunction "2_2") (pintype "passive"))
    )
    (net (code "20") (name "Net-(C23-Pad1)") (class "Default")
      (node (ref "C23") (pin "1") (pinfunction "1_1") (pintype "passive"))
      (node (ref "R27") (pin "2") (pinfunction "2_2") (pintype "passive"))
    )
    (net (code "21") (name "Net-(C36-Pad2)") (class "Default")
      (node (ref "C36") (pin "2") (pinfunction "2_2") (pintype "passive"))
      (node (ref "L6") (pin "2") (pinfunction "2_2") (pintype "passive"))
      (node (ref "L7") (pin "1") (pinfunction "1_1") (pintype "passive"))
    )
    (net (code "22") (name "Net-(C38-Pad2)") (class "Default")
      (node (ref "C38") (pin "2") (pinfunction "2_2") (pintype "passive"))
      (node (ref "P1") (pin "1") (pinfunction "1_1") (pintype "passive"))
    )
    (net (code "23") (name "Net-(D1-A)") (class "Default")
      (node (ref "C38") (pin "1") (pinfunction "1_1") (pintype "passive"))
      (node (ref "D1") (pin "2") (pinfunction "A_2") (pintype "passive"))
      (node (ref "IC1") (pin "2") (pinfunction "RF_IN_2") (pintype "input"))
      (node (ref "IC1") (pin "3") (pinfunction "RF_IN_3") (pintype "input"))
      (node (ref "L2") (pin "2") (pinfunction "2_2") (pintype "passive"))
      (node (ref "R5") (pin "1") (pinfunction "1_1") (pintype "passive"))
    )
    (net (code "24") (name "Net-(D2-A)") (class "Default")
      (node (ref "D2") (pin "2") (pinfunction "A_2") (pintype "passive"))
      (node (ref "D4") (pin "1") (pinfunction "C_1") (pintype "passive"))
    )
    (net (code "25") (name "Net-(D2-C)") (class "Default")
      (node (ref "D2") (pin "1") (pinfunction "C_1") (pintype "passive"))
      (node (ref "D3") (pin "2") (pinfunction "C_2") (pintype "passive"))
    )
    (net (code "26") (name "Net-(D3A-COMAC)") (class "Default")
      (node (ref "C1") (pin "2") (pinfunction "2_2") (pintype "passive"))
      (node (ref "D3") (pin "3") (pinfunction "COMAC_3") (pintype "passive"))
      (node (ref "IC1") (pin "6") (pinfunction "RF_OUT_6") (pintype "output"))
      (node (ref "IC1") (pin "7") (pinfunction "RF_OUT_7") (pintype "output"))
      (node (ref "L3") (pin "1") (pinfunction "1_1") (pintype "passive"))
      (node (ref "L6") (pin "1") (pinfunction "1_1") (pintype "passive"))
    )
    (net (code "27") (name "Net-(IC2-CPL_F)") (class "Default")
      (node (ref "C11") (pin "2") (pinfunction "2_2") (pintype "passive"))
      (node (ref "IC2") (pin "5") (pinfunction "CPL_F_5") (pintype "output"))
    )
    (net (code "28") (name "Net-(IC2-CPL_R)") (class "Default")
      (node (ref "C10") (pin "2") (pinfunction "2_2") (pintype "passive"))
      (node (ref "IC2") (pin "4") (pinfunction "CPL_R_4") (pintype "output"))
    )
    (net (code "29") (name "Net-(IC2-IN)") (class "Default")
      (node (ref "C37") (pin "2") (pinfunction "2_2") (pintype "passive"))
      (node (ref "C9") (pin "2") (pinfunction "2_2") (pintype "passive"))
      (node (ref "IC2") (pin "8") (pinfunction "IN_8") (pintype "input"))
    )
    (net (code "30") (name "Net-(IC2-OUT)") (class "Default")
      (node (ref "C12") (pin "2") (pinfunction "2_2") (pintype "passive"))
      (node (ref "IC2") (pin "1") (pinfunction "OUT_1") (pintype "output"))
    )
    (net (code "31") (name "Net-(IC3-CRMS)") (class "Default")
      (node (ref "C19") (pin "1") (pinfunction "1_1") (pintype "passive"))
      (node (ref "IC3") (pin "9") (pinfunction "CRMS_9") (pintype "input"))
    )
    (net (code "32") (name "Net-(IC3-DECL)") (class "Default")
      (node (ref "C19") (pin "2") (pinfunction "2_2") (pintype "passive"))
      (node (ref "IC3") (pin "4") (pinfunction "DECL_4") (pintype "input"))
      (node (ref "R26") (pin "1") (pinfunction "1_1") (pintype "passive"))
    )
    (net (code "33") (name "Net-(IC3-ENBL)") (class "Default")
      (node (ref "IC3") (pin "14") (pinfunction "ENBL_14") (pintype "input"))
      (node (ref "R18") (pin "2") (pinfunction "2_2") (pintype "passive"))
    )
    (net (code "34") (name "Net-(IC3-Q)") (class "Default")
      (node (ref "IC3") (pin "12") (pinfunction "Q_12") (pintype "output"))
      (node (ref "R25") (pin "2") (pinfunction "2_2") (pintype "passive"))
    )
    (net (code "35") (name "Net-(IC3-RFIN)") (class "Default")
      (node (ref "C15") (pin "1") (pinfunction "1_1") (pintype "passive"))
      (node (ref "IC3") (pin "1") (pinfunction "RFIN_1") (pintype "input"))
    )
    (net (code "36") (name "Net-(IC3-RST)") (class "Default")
      (node (ref "IC3") (pin "15") (pinfunction "RST_15") (pintype "input"))
      (node (ref "R21") (pin "2") (pinfunction "2_2") (pintype "passive"))
      (node (ref "R7") (pin "1") (pinfunction "1_1") (pintype "passive"))
    )
    (net (code "37") (name "Net-(IC3-VIN-)") (class "Default")
      (node (ref "C30") (pin "2") (pinfunction "2_2") (pintype "passive"))
      (node (ref "IC3") (pin "16") (pinfunction "VIN-_16") (pintype "input"))
      (node (ref "R20") (pin "2") (pinfunction "2_2") (pintype "passive"))
      (node (ref "R40") (pin "1") (pinfunction "1_1") (pintype "passive"))
    )
    (net (code "38") (name "Net-(IC3-VRMS)") (class "Default")
      (node (ref "IC3") (pin "10") (pinfunction "VRMS_10") (pintype "output"))
      (node (ref "R29") (pin "2") (pinfunction "2_2") (pintype "passive"))
    )
    (net (code "39") (name "Net-(IC3-~{Q})") (class "Default")
      (node (ref "IC3") (pin "13") (pinfunction "~{Q}_13") (pintype "output"))
      (node (ref "R38") (pin "2") (pinfunction "2_2") (pintype "passive"))
    )
    (net (code "40") (name "Net-(IC4-CRMS)") (class "Default")
      (node (ref "C22") (pin "1") (pinfunction "1_1") (pintype "passive"))
      (node (ref "IC4") (pin "9") (pinfunction "CRMS_9") (pintype "input"))
    )
    (net (code "41") (name "Net-(IC4-DECL)") (class "Default")
      (node (ref "C22") (pin "2") (pinfunction "2_2") (pintype "passive"))
      (node (ref "IC4") (pin "4") (pinfunction "DECL_4") (pintype "input"))
      (node (ref "R27") (pin "1") (pinfunction "1_1") (pintype "passive"))
    )
    (net (code "42") (name "Net-(IC4-ENBL)") (class "Default")
      (node (ref "IC4") (pin "14") (pinfunction "ENBL_14") (pintype "input"))
      (node (ref "R19") (pin "1") (pinfunction "1_1") (pintype "passive"))
    )
    (net (code "43") (name "Net-(IC4-Q)") (class "Default")
      (node (ref "IC4") (pin "12") (pinfunction "Q_12") (pintype "output"))
      (node (ref "R37") (pin "2") (pinfunction "2_2") (pintype "passive"))
    )
    (net (code "44") (name "Net-(IC4-RFIN)") (class "Default")
      (node (ref "C16") (pin "1") (pinfunction "1_1") (pintype "passive"))
      (node (ref "IC4") (pin "1") (pinfunction "RFIN_1") (pintype "input"))
    )
    (net (code "45") (name "Net-(IC4-RST)") (class "Default")
      (node (ref "IC4") (pin "15") (pinfunction "RST_15") (pintype "input"))
      (node (ref "R2") (pin "1") (pinfunction "1_1") (pintype "passive"))
      (node (ref "R9") (pin "2") (pinfunction "2_2") (pintype "passive"))
    )
    (net (code "46") (name "Net-(IC4-VIN-)") (class "Default")
      (node (ref "C25") (pin "2") (pinfunction "2_2") (pintype "passive"))
      (node (ref "IC4") (pin "16") (pinfunction "VIN-_16") (pintype "input"))
      (node (ref "R24") (pin "2") (pinfunction "2_2") (pintype "passive"))
      (node (ref "R28") (pin "1") (pinfunction "1_1") (pintype "passive"))
    )
    (net (code "47") (name "Net-(IC4-VRMS)") (class "Default")
      (node (ref "IC4") (pin "10") (pinfunction "VRMS_10") (pintype "output"))
      (node (ref "R30") (pin "2") (pinfunction "2_2") (pintype "passive"))
    )
    (net (code "48") (name "Net-(IC4-~{Q})") (class "Default")
      (node (ref "IC4") (pin "13") (pinfunction "~{Q}_13") (pintype "output"))
      (node (ref "R39") (pin "2") (pinfunction "2_2") (pintype "passive"))
    )
    (net (code "49") (name "Net-(IC5-IN+)") (class "Default")
      (node (ref "C26") (pin "2") (pinfunction "2_2") (pintype "passive"))
      (node (ref "IC5") (pin "3") (pinfunction "IN+_3") (pintype "input"))
      (node (ref "R29") (pin "1") (pinfunction "1_1") (pintype "passive"))
    )
    (net (code "50") (name "Net-(IC5-IN-)") (class "Default")
      (node (ref "IC5") (pin "4") (pinfunction "IN-_4") (pintype "input"))
      (node (ref "R22") (pin "2") (pinfunction "2_2") (pintype "passive"))
      (node (ref "R31") (pin "2") (pinfunction "2_2") (pintype "passive"))
    )
    (net (code "51") (name "Net-(IC5-OUT)") (class "Default")
      (node (ref "IC5") (pin "1") (pinfunction "OUT_1") (pintype "output"))
      (node (ref "R22") (pin "1") (pinfunction "1_1") (pintype "passive"))
      (node (ref "R41") (pin "2") (pinfunction "2_2") (pintype "passive"))
      (node (ref "R42") (pin "2") (pinfunction "2_2") (pintype "passive"))
    )
    (net (code "52") (name "Net-(IC5-V+)") (class "Default")
      (node (ref "C21") (pin "2") (pinfunction "2_2") (pintype "passive"))
      (node (ref "IC5") (pin "5") (pinfunction "V+_5") (pintype "power_in"))
      (node (ref "L1") (pin "1") (pinfunction "1_1") (pintype "passive"))
    )
    (net (code "53") (name "Net-(IC6-IN+)") (class "Default")
      (node (ref "C27") (pin "2") (pinfunction "2_2") (pintype "passive"))
      (node (ref "IC6") (pin "3") (pinfunction "IN+_3") (pintype "input"))
      (node (ref "R30") (pin "1") (pinfunction "1_1") (pintype "passive"))
    )
    (net (code "54") (name "Net-(IC6-IN-)") (class "Default")
      (node (ref "IC6") (pin "4") (pinfunction "IN-_4") (pintype "input"))
      (node (ref "R23") (pin "2") (pinfunction "2_2") (pintype "passive"))
      (node (ref "R32") (pin "2") (pinfunction "2_2") (pintype "passive"))
    )
    (net (code "55") (name "Net-(IC6-OUT)") (class "Default")
      (node (ref "IC6") (pin "1") (pinfunction "OUT_1") (pintype "output"))
      (node (ref "R12") (pin "1") (pinfunction "1_1") (pintype "passive"))
      (node (ref "R17") (pin "1") (pinfunction "1_1") (pintype "passive"))
      (node (ref "R23") (pin "1") (pinfunction "1_1") (pintype "passive"))
    )
    (net (code "56") (name "Net-(IC6-V+)") (class "Default")
      (node (ref "C24") (pin "2") (pinfunction "2_2") (pintype "passive"))
      (node (ref "IC6") (pin "5") (pinfunction "V+_5") (pintype "power_in"))
      (node (ref "L4") (pin "1") (pinfunction "1_1") (pintype "passive"))
    )
    (net (code "57") (name "Net-(IC7-DXP)") (class "Default")
      (node (ref "C35") (pin "2") (pinfunction "2_2") (pintype "passive"))
      (node (ref "IC7") (pin "3") (pinfunction "DXP_3") (pintype "input"))
      (node (ref "T2") (pin "2") (pinfunction "E_2") (pintype "passive"))
    )
    (net (code "58") (name "Net-(IC7-VCC)") (class "Default")
      (node (ref "C29") (pin "2") (pinfunction "2_2") (pintype "passive"))
      (node (ref "IC7") (pin "1") (pinfunction "VCC_1") (pintype "power_in"))
      (node (ref "R33") (pin "1") (pinfunction "1_1") (pintype "passive"))
    )
    (net (code "59") (name "OUT_BIAS") (class "Default")
      (node (ref "P6") (pin "8") (pinfunction "8_8") (pintype "passive"))
      (node (ref "R1") (pin "2") (pinfunction "2_2") (pintype "passive"))
    )
    (net (code "60") (name "P3V3") (class "Default")
      (node (ref "C13") (pin "2") (pinfunction "2_2") (pintype "passive"))
      (node (ref "P6") (pin "6") (pinfunction "6_6") (pintype "passive"))
      (node (ref "R3") (pin "1") (pinfunction "1_1") (pintype "passive"))
      (node (ref "R33") (pin "2") (pinfunction "2_2") (pintype "passive"))
      (node (ref "R34") (pin "1") (pinfunction "1_1") (pintype "passive"))
      (node (ref "R35") (pin "1") (pinfunction "1_1") (pintype "passive"))
      (node (ref "R36") (pin "1") (pinfunction "1_1") (pintype "passive"))
      (node (ref "R6") (pin "1") (pinfunction "1_1") (pintype "passive"))
      (node (ref "U8") (pin "4") (pinfunction "VCC_4") (pintype "passive"))
    )
    (net (code "61") (name "P3V3A") (class "Default")
      (node (ref "C14") (pin "2") (pinfunction "2_2") (pintype "passive"))
      (node (ref "C17") (pin "2") (pinfunction "2_2") (pintype "passive"))
      (node (ref "C8") (pin "2") (pinfunction "2_2") (pintype "passive"))
      (node (ref "IC3") (pin "5") (pinfunction "VPOS_5") (pintype "power_in"))
      (node (ref "IC3") (pin "7") (pinfunction "VPOS_7") (pintype "power_in"))
      (node (ref "IC4") (pin "5") (pinfunction "VPOS_5") (pintype "power_in"))
      (node (ref "IC4") (pin "7") (pinfunction "VPOS_7") (pintype "power_in"))
      (node (ref "L1") (pin "2") (pinfunction "2_2") (pintype "passive"))
      (node (ref "L4") (pin "2") (pinfunction "2_2") (pintype "passive"))
      (node (ref "P3") (pin "8") (pinfunction "8_8") (pintype "passive"))
      (node (ref "R18") (pin "1") (pinfunction "1_1") (pintype "passive"))
      (node (ref "R19") (pin "2") (pinfunction "2_2") (pintype "passive"))
    )
    (net (code "62") (name "VCC_PWRAMP") (class "Default")
      (node (ref "C5") (pin "2") (pinfunction "2_2") (pintype "passive"))
      (node (ref "C6") (pin "2") (pinfunction "2_2") (pintype "passive"))
      (node (ref "C7") (pin "2") (pinfunction "2_2") (pintype "passive"))
      (node (ref "L3") (pin "2") (pinfunction "2_2") (pintype "passive"))
      (node (ref "P6") (pin "2") (pinfunction "2_2") (pintype "passive"))
      (node (ref "P6") (pin "4") (pinfunction "4_4") (pintype "passive"))
    )
    (net (code "63") (name "unconnected-(D3A-A-Pad1)") (class "Default")
      (node (ref "D3") (pin "1") (pinfunction "A_1") (pintype "passive"))
    )
    (net (code "64") (name "unconnected-(IC1-NC-Pad1)") (class "Default")
      (node (ref "IC1") (pin "1") (pinfunction "NC_1") (pintype "passive"))
    )
    (net (code "65") (name "unconnected-(IC1-NC-Pad4)") (class "Default")
      (node (ref "IC1") (pin "4") (pinfunction "NC_4") (pintype "passive"))
    )
    (net (code "66") (name "unconnected-(IC1-NC-Pad5)") (class "Default")
      (node (ref "IC1") (pin "5") (pinfunction "NC_5") (pintype "power_in"))
    )
    (net (code "67") (name "unconnected-(IC1-NC-Pad8)") (class "Default")
      (node (ref "IC1") (pin "8") (pinfunction "NC_8") (pintype "power_in"))
    )
    (net (code "68") (name "unconnected-(IC3-DNC-Pad2)") (class "Default")
      (node (ref "IC3") (pin "2") (pinfunction "DNC_2") (pintype "passive+no_connect"))
    )
    (net (code "69") (name "unconnected-(IC3-DNC-Pad6)") (class "Default")
      (node (ref "IC3") (pin "6") (pinfunction "DNC_6") (pintype "passive+no_connect"))
    )
    (net (code "70") (name "unconnected-(IC3-DNC-Pad8)") (class "Default")
      (node (ref "IC3") (pin "8") (pinfunction "DNC_8") (pintype "passive+no_connect"))
    )
    (net (code "71") (name "unconnected-(IC3-VCAL-Pad3)") (class "Default")
      (node (ref "IC3") (pin "3") (pinfunction "VCAL_3") (pintype "input+no_connect"))
    )
    (net (code "72") (name "unconnected-(IC4-DNC-Pad2)") (class "Default")
      (node (ref "IC4") (pin "2") (pinfunction "DNC_2") (pintype "passive+no_connect"))
    )
    (net (code "73") (name "unconnected-(IC4-DNC-Pad6)") (class "Default")
      (node (ref "IC4") (pin "6") (pinfunction "DNC_6") (pintype "passive+no_connect"))
    )
    (net (code "74") (name "unconnected-(IC4-DNC-Pad8)") (class "Default")
      (node (ref "IC4") (pin "8") (pinfunction "DNC_8") (pintype "passive+no_connect"))
    )
    (net (code "75") (name "unconnected-(IC4-VCAL-Pad3)") (class "Default")
      (node (ref "IC4") (pin "3") (pinfunction "VCAL_3") (pintype "input+no_connect"))
    )
  )
)
